# gps10mhz.net
KiCad netlist of a schematic drawn in EAGLE
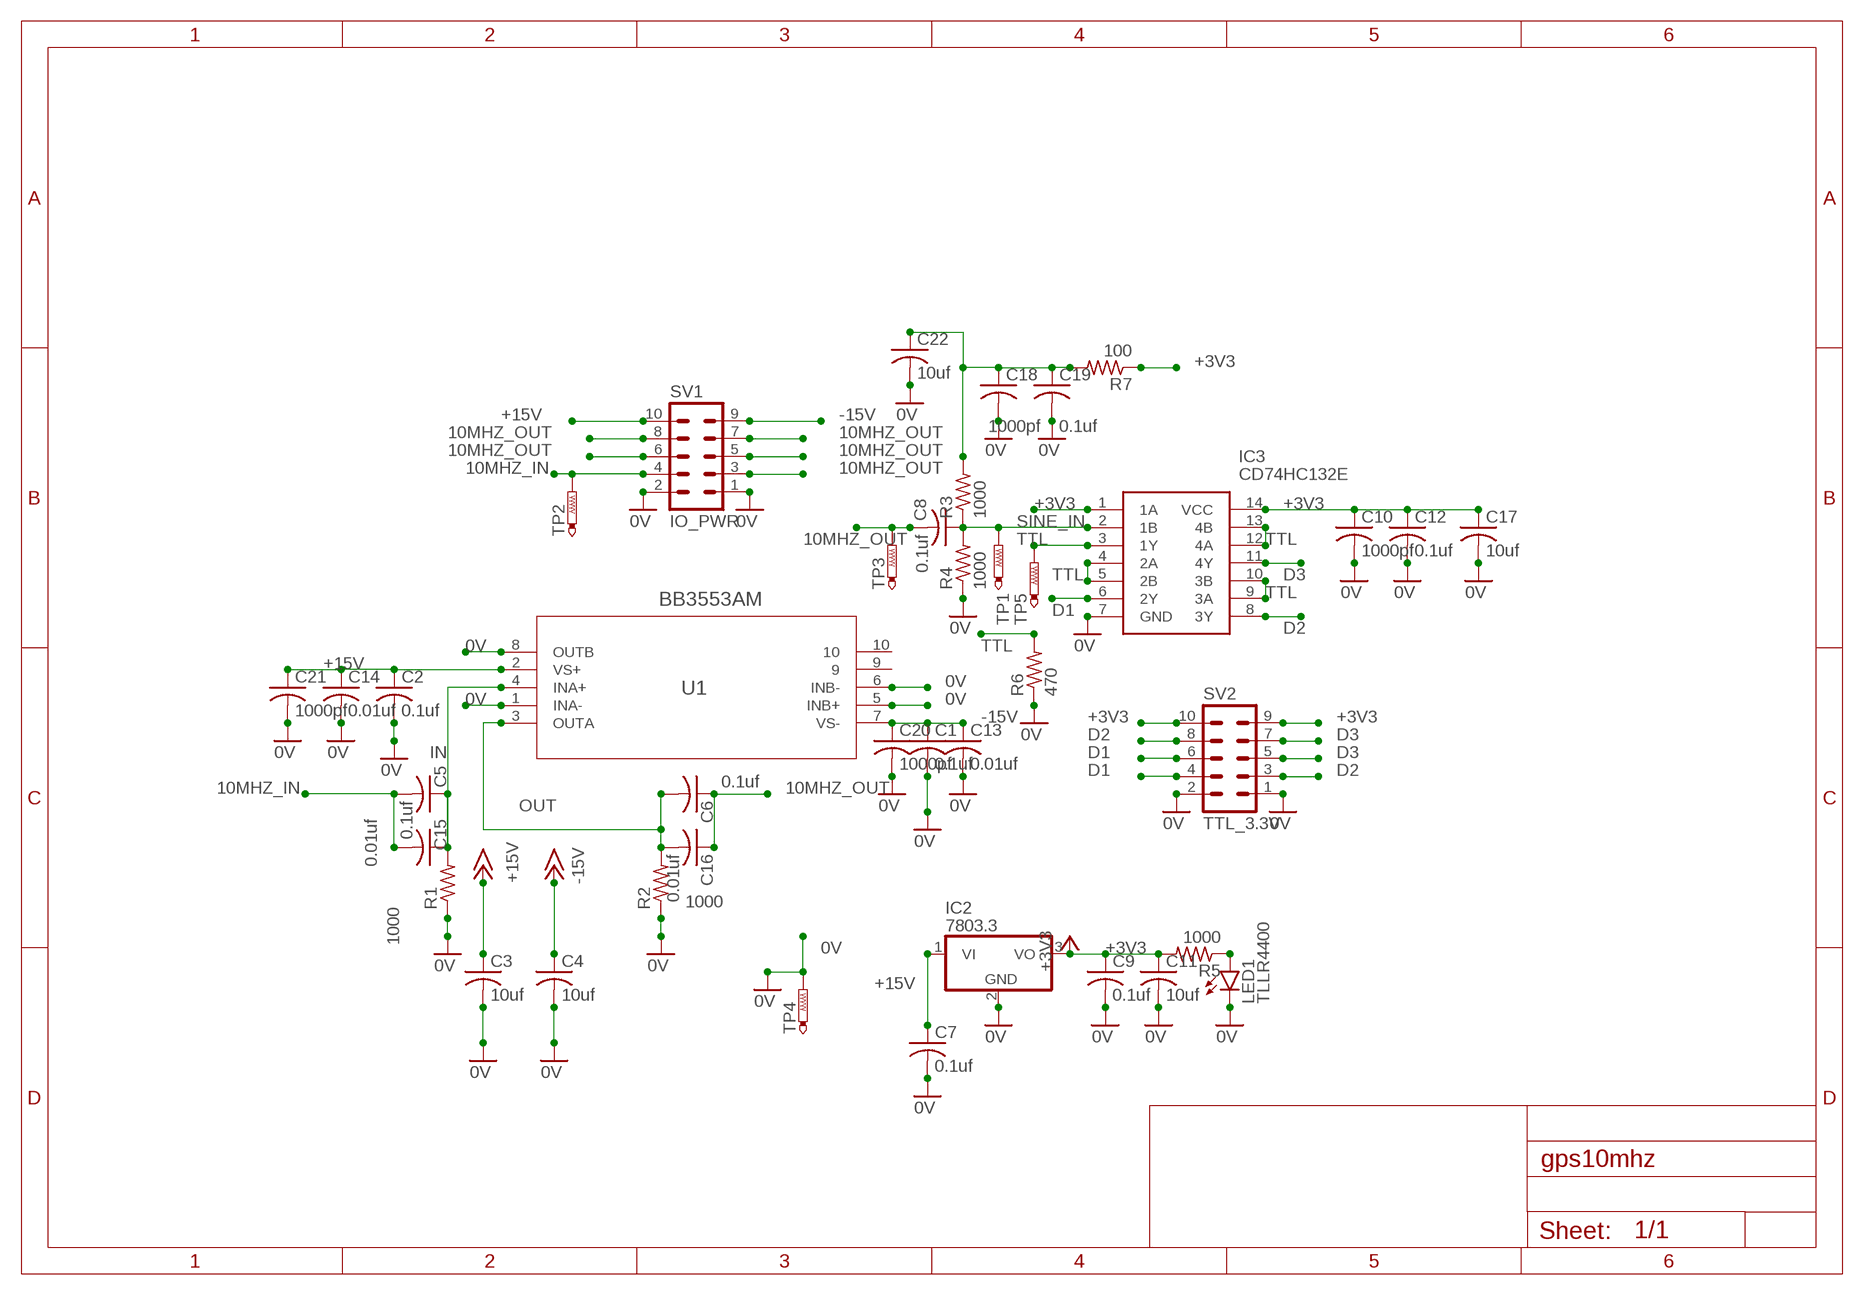
[diagram p0: schematic, sheet 1]

(export (version "E")
  (design (tool "Eeschema 10.0.6"))
  (components
    (comp (ref "C1")
      (value "0.1uf")
      (footprint "eagle-import:C0805")
      (libsource (lib "eagle-import") (part "C-USC0805"))
    )
    (comp (ref "C2")
      (value "0.1uf")
      (footprint "eagle-import:C0805")
      (libsource (lib "eagle-import") (part "C-USC0805"))
    )
    (comp (ref "C3")
      (value "10uf")
      (footprint "eagle-import:C0805")
      (libsource (lib "eagle-import") (part "C-USC0805"))
    )
    (comp (ref "C4")
      (value "10uf")
      (footprint "eagle-import:C0805")
      (libsource (lib "eagle-import") (part "C-USC0805"))
    )
    (comp (ref "C5")
      (value "0.1uf")
      (footprint "eagle-import:C0805")
      (libsource (lib "eagle-import") (part "C-USC0805"))
    )
    (comp (ref "C6")
      (value "0.1uf")
      (footprint "eagle-import:C0805")
      (libsource (lib "eagle-import") (part "C-USC0805"))
    )
    (comp (ref "C7")
      (value "0.1uf")
      (footprint "eagle-import:C0805")
      (libsource (lib "eagle-import") (part "C-USC0805"))
    )
    (comp (ref "C8")
      (value "0.1uf")
      (footprint "eagle-import:C0805")
      (libsource (lib "eagle-import") (part "C-USC0805"))
    )
    (comp (ref "C9")
      (value "0.1uf")
      (footprint "eagle-import:C0805")
      (libsource (lib "eagle-import") (part "C-USC0805"))
    )
    (comp (ref "C10")
      (value "1000pf")
      (footprint "eagle-import:C0805")
      (libsource (lib "eagle-import") (part "C-USC0805"))
    )
    (comp (ref "C11")
      (value "10uf")
      (footprint "eagle-import:C0805")
      (libsource (lib "eagle-import") (part "C-USC0805"))
    )
    (comp (ref "C12")
      (value "0.1uf")
      (footprint "eagle-import:C0805")
      (libsource (lib "eagle-import") (part "C-USC0805"))
    )
    (comp (ref "C13")
      (value "0.01uf")
      (footprint "eagle-import:C0805")
      (libsource (lib "eagle-import") (part "C-USC0805"))
    )
    (comp (ref "C14")
      (value "0.01uf")
      (footprint "eagle-import:C0805")
      (libsource (lib "eagle-import") (part "C-USC0805"))
    )
    (comp (ref "C15")
      (value "0.01uf")
      (footprint "eagle-import:C0805")
      (libsource (lib "eagle-import") (part "C-USC0805"))
    )
    (comp (ref "C16")
      (value "0.01uf")
      (footprint "eagle-import:C0805")
      (libsource (lib "eagle-import") (part "C-USC0805"))
    )
    (comp (ref "C17")
      (value "10uf")
      (footprint "eagle-import:C0805")
      (libsource (lib "eagle-import") (part "C-USC0805"))
    )
    (comp (ref "C18")
      (value "1000pf")
      (footprint "eagle-import:C0805")
      (libsource (lib "eagle-import") (part "C-USC0805"))
    )
    (comp (ref "C19")
      (value "0.1uf")
      (footprint "eagle-import:C0805")
      (libsource (lib "eagle-import") (part "C-USC0805"))
    )
    (comp (ref "C20")
      (value "1000pf")
      (footprint "eagle-import:C0805")
      (libsource (lib "eagle-import") (part "C-USC0805"))
    )
    (comp (ref "C21")
      (value "1000pf")
      (footprint "eagle-import:C0805")
      (libsource (lib "eagle-import") (part "C-USC0805"))
    )
    (comp (ref "C22")
      (value "10uf")
      (footprint "eagle-import:C0805")
      (libsource (lib "eagle-import") (part "C-USC0805"))
    )
    (comp (ref "IC2")
      (value "7803.3")
      (footprint "eagle-import:TO220H")
      (libsource (lib "eagle-import") (part "78T05"))
    )
    (comp (ref "IC3")
      (value "CD74HC132E")
      (footprint "eagle-import:DIP794W53P254L1930H508Q14N")
      (fields (field (name "MOUSER_PART_NUMBER") "595-CD74HC132E"))
      (libsource (lib "eagle-import") (part "CD74HC132E"))
    )
    (comp (ref "LED1")
      (value "TLLR4400")
      (footprint "eagle-import:LED3MM")
      (fields (field (name "MF") "VISHAY SEMICONDUCTOR"))
      (libsource (lib "eagle-import") (part "TLLR4400"))
    )
    (comp (ref "R1")
      (value "1000")
      (footprint "eagle-import:R1206")
      (libsource (lib "eagle-import") (part "R-US_R1206"))
    )
    (comp (ref "R2")
      (value "1000")
      (footprint "eagle-import:R1206")
      (libsource (lib "eagle-import") (part "R-US_R1206"))
    )
    (comp (ref "R3")
      (value "1000")
      (footprint "eagle-import:R1206")
      (libsource (lib "eagle-import") (part "R-US_R1206"))
    )
    (comp (ref "R4")
      (value "1000")
      (footprint "eagle-import:R1206")
      (libsource (lib "eagle-import") (part "R-US_R1206"))
    )
    (comp (ref "R5")
      (value "1000")
      (footprint "eagle-import:R1206")
      (libsource (lib "eagle-import") (part "R-US_R1206"))
    )
    (comp (ref "R6")
      (value "470")
      (footprint "eagle-import:R1206")
      (libsource (lib "eagle-import") (part "R-US_R1206"))
    )
    (comp (ref "R7")
      (value "100")
      (footprint "eagle-import:R1206")
      (libsource (lib "eagle-import") (part "R-US_R1206"))
    )
    (comp (ref "SV1")
      (value "IO_PWR")
      (footprint "eagle-import:MA05-2")
      (libsource (lib "eagle-import") (part "MA05-2"))
    )
    (comp (ref "SV2")
      (value "TTL_3.3V")
      (footprint "eagle-import:MA05-2")
      (libsource (lib "eagle-import") (part "MA05-2"))
    )
    (comp (ref "TP1")
      (value "PTR1PAD1-13")
      (footprint "eagle-import:P1-13")
      (libsource (lib "eagle-import") (part "PTR1PAD1-13"))
    )
    (comp (ref "TP2")
      (value "PTR1PAD1-13")
      (footprint "eagle-import:P1-13")
      (libsource (lib "eagle-import") (part "PTR1PAD1-13"))
    )
    (comp (ref "TP3")
      (value "PTR1PAD1-13")
      (footprint "eagle-import:P1-13")
      (libsource (lib "eagle-import") (part "PTR1PAD1-13"))
    )
    (comp (ref "TP4")
      (value "PTR1PAD1-13")
      (footprint "eagle-import:P1-13")
      (libsource (lib "eagle-import") (part "PTR1PAD1-13"))
    )
    (comp (ref "TP5")
      (value "PTR1PAD1-13")
      (footprint "eagle-import:P1-13")
      (libsource (lib "eagle-import") (part "PTR1PAD1-13"))
    )
    (comp (ref "U1")
      (value "BB3553AM")
      (footprint "eagle-import:LMF8_TEX")
      (fields
        (field (name "MANUFACTURER_PART_NUMBER") "OPA2541AM")
        (field (name "COPYRIGHT") "Copyright (C) 2025 Ultra Librarian. All rights reserved.")
      )
      (libsource (lib "eagle-import") (part "OPA2541AMBB3553AM"))
    )
  )
  (nets
    (net (code "1") (name "+3V3") (class "Default")
      (node (ref "C10") (pin "1") (pinfunction "1_1") (pintype "passive"))
      (node (ref "C11") (pin "1") (pinfunction "1_1") (pintype "passive"))
      (node (ref "C12") (pin "1") (pinfunction "1_1") (pintype "passive"))
      (node (ref "C17") (pin "1") (pinfunction "1_1") (pintype "passive"))
      (node (ref "C9") (pin "1") (pinfunction "1_1") (pintype "passive"))
      (node (ref "IC2") (pin "3") (pinfunction "VO_3") (pintype "passive"))
      (node (ref "IC3") (pin "1") (pinfunction "1A_1") (pintype "bidirectional"))
      (node (ref "IC3") (pin "14") (pinfunction "VCC_14") (pintype "bidirectional"))
      (node (ref "R5") (pin "2") (pinfunction "2_2") (pintype "passive"))
      (node (ref "R7") (pin "1") (pinfunction "1_1") (pintype "passive"))
      (node (ref "SV2") (pin "10") (pinfunction "10_10") (pintype "passive"))
      (node (ref "SV2") (pin "9") (pinfunction "9_9") (pintype "passive"))
    )
    (net (code "2") (name "+15V") (class "Default")
      (node (ref "C14") (pin "1") (pinfunction "1_1") (pintype "passive"))
      (node (ref "C2") (pin "1") (pinfunction "1_1") (pintype "passive"))
      (node (ref "C21") (pin "1") (pinfunction "1_1") (pintype "passive"))
      (node (ref "C3") (pin "1") (pinfunction "1_1") (pintype "passive"))
      (node (ref "C7") (pin "1") (pinfunction "1_1") (pintype "passive"))
      (node (ref "IC2") (pin "1") (pinfunction "VI_1") (pintype "input"))
      (node (ref "SV1") (pin "10") (pinfunction "10_10") (pintype "passive"))
      (node (ref "U1") (pin "2") (pinfunction "VS+_2") (pintype "power_in"))
    )
    (net (code "3") (name "-15V") (class "Default")
      (node (ref "C1") (pin "1") (pinfunction "1_1") (pintype "passive"))
      (node (ref "C13") (pin "1") (pinfunction "1_1") (pintype "passive"))
      (node (ref "C20") (pin "1") (pinfunction "1_1") (pintype "passive"))
      (node (ref "C4") (pin "1") (pinfunction "1_1") (pintype "passive"))
      (node (ref "SV1") (pin "9") (pinfunction "9_9") (pintype "passive"))
      (node (ref "U1") (pin "7") (pinfunction "VS-_7") (pintype "power_in"))
    )
    (net (code "4") (name "/10MHZ_IN") (class "Default")
      (node (ref "C15") (pin "2") (pinfunction "2_2") (pintype "passive"))
      (node (ref "C5") (pin "2") (pinfunction "2_2") (pintype "passive"))
      (node (ref "SV1") (pin "4") (pinfunction "4_4") (pintype "passive"))
      (node (ref "TP2") (pin "TP") (pinfunction "TP_TP") (pintype "input"))
    )
    (net (code "5") (name "/10MHZ_OUT") (class "Default")
      (node (ref "C16") (pin "1") (pinfunction "1_1") (pintype "passive"))
      (node (ref "C6") (pin "1") (pinfunction "1_1") (pintype "passive"))
      (node (ref "C8") (pin "2") (pinfunction "2_2") (pintype "passive"))
      (node (ref "SV1") (pin "3") (pinfunction "3_3") (pintype "passive"))
      (node (ref "SV1") (pin "5") (pinfunction "5_5") (pintype "passive"))
      (node (ref "SV1") (pin "6") (pinfunction "6_6") (pintype "passive"))
      (node (ref "SV1") (pin "7") (pinfunction "7_7") (pintype "passive"))
      (node (ref "SV1") (pin "8") (pinfunction "8_8") (pintype "passive"))
      (node (ref "TP3") (pin "TP") (pinfunction "TP_TP") (pintype "input"))
    )
    (net (code "6") (name "/D1") (class "Default")
      (node (ref "IC3") (pin "6") (pinfunction "2Y_6") (pintype "bidirectional"))
      (node (ref "SV2") (pin "4") (pinfunction "4_4") (pintype "passive"))
      (node (ref "SV2") (pin "6") (pinfunction "6_6") (pintype "passive"))
    )
    (net (code "7") (name "/D2") (class "Default")
      (node (ref "IC3") (pin "8") (pinfunction "3Y_8") (pintype "bidirectional"))
      (node (ref "SV2") (pin "3") (pinfunction "3_3") (pintype "passive"))
      (node (ref "SV2") (pin "8") (pinfunction "8_8") (pintype "passive"))
    )
    (net (code "8") (name "/D3") (class "Default")
      (node (ref "IC3") (pin "11") (pinfunction "4Y_11") (pintype "bidirectional"))
      (node (ref "SV2") (pin "5") (pinfunction "5_5") (pintype "passive"))
      (node (ref "SV2") (pin "7") (pinfunction "7_7") (pintype "passive"))
    )
    (net (code "9") (name "/IN") (class "Default")
      (node (ref "C15") (pin "1") (pinfunction "1_1") (pintype "passive"))
      (node (ref "C5") (pin "1") (pinfunction "1_1") (pintype "passive"))
      (node (ref "R1") (pin "2") (pinfunction "2_2") (pintype "passive"))
      (node (ref "U1") (pin "4") (pinfunction "INA+_4") (pintype "input"))
    )
    (net (code "10") (name "/OUT") (class "Default")
      (node (ref "C16") (pin "2") (pinfunction "2_2") (pintype "passive"))
      (node (ref "C6") (pin "2") (pinfunction "2_2") (pintype "passive"))
      (node (ref "R2") (pin "2") (pinfunction "2_2") (pintype "passive"))
      (node (ref "U1") (pin "3") (pinfunction "OUTA_3") (pintype "output"))
    )
    (net (code "11") (name "/SINE_IN") (class "Default")
      (node (ref "C8") (pin "1") (pinfunction "1_1") (pintype "passive"))
      (node (ref "IC3") (pin "2") (pinfunction "1B_2") (pintype "bidirectional"))
      (node (ref "R3") (pin "1") (pinfunction "1_1") (pintype "passive"))
      (node (ref "R4") (pin "2") (pinfunction "2_2") (pintype "passive"))
      (node (ref "TP1") (pin "TP") (pinfunction "TP_TP") (pintype "input"))
    )
    (net (code "12") (name "/TTL") (class "Default")
      (node (ref "IC3") (pin "10") (pinfunction "3B_10") (pintype "bidirectional"))
      (node (ref "IC3") (pin "12") (pinfunction "4A_12") (pintype "bidirectional"))
      (node (ref "IC3") (pin "13") (pinfunction "4B_13") (pintype "bidirectional"))
      (node (ref "IC3") (pin "3") (pinfunction "1Y_3") (pintype "bidirectional"))
      (node (ref "IC3") (pin "4") (pinfunction "2A_4") (pintype "bidirectional"))
      (node (ref "IC3") (pin "5") (pinfunction "2B_5") (pintype "bidirectional"))
      (node (ref "IC3") (pin "9") (pinfunction "3A_9") (pintype "bidirectional"))
      (node (ref "R6") (pin "2") (pinfunction "2_2") (pintype "passive"))
      (node (ref "TP5") (pin "TP") (pinfunction "TP_TP") (pintype "input"))
    )
    (net (code "13") (name "0V") (class "Default")
      (node (ref "C1") (pin "2") (pinfunction "2_2") (pintype "passive"))
      (node (ref "C10") (pin "2") (pinfunction "2_2") (pintype "passive"))
      (node (ref "C11") (pin "2") (pinfunction "2_2") (pintype "passive"))
      (node (ref "C12") (pin "2") (pinfunction "2_2") (pintype "passive"))
      (node (ref "C13") (pin "2") (pinfunction "2_2") (pintype "passive"))
      (node (ref "C14") (pin "2") (pinfunction "2_2") (pintype "passive"))
      (node (ref "C17") (pin "2") (pinfunction "2_2") (pintype "passive"))
      (node (ref "C18") (pin "2") (pinfunction "2_2") (pintype "passive"))
      (node (ref "C19") (pin "2") (pinfunction "2_2") (pintype "passive"))
      (node (ref "C2") (pin "2") (pinfunction "2_2") (pintype "passive"))
      (node (ref "C20") (pin "2") (pinfunction "2_2") (pintype "passive"))
      (node (ref "C21") (pin "2") (pinfunction "2_2") (pintype "passive"))
      (node (ref "C22") (pin "2") (pinfunction "2_2") (pintype "passive"))
      (node (ref "C3") (pin "2") (pinfunction "2_2") (pintype "passive"))
      (node (ref "C4") (pin "2") (pinfunction "2_2") (pintype "passive"))
      (node (ref "C7") (pin "2") (pinfunction "2_2") (pintype "passive"))
      (node (ref "C9") (pin "2") (pinfunction "2_2") (pintype "passive"))
      (node (ref "IC2") (pin "2") (pinfunction "GND_2") (pintype "passive"))
      (node (ref "IC3") (pin "7") (pinfunction "GND_7") (pintype "bidirectional"))
      (node (ref "LED1") (pin "K") (pinfunction "C_K") (pintype "passive"))
      (node (ref "R1") (pin "1") (pinfunction "1_1") (pintype "passive"))
      (node (ref "R2") (pin "1") (pinfunction "1_1") (pintype "passive"))
      (node (ref "R4") (pin "1") (pinfunction "1_1") (pintype "passive"))
      (node (ref "R6") (pin "1") (pinfunction "1_1") (pintype "passive"))
      (node (ref "SV1") (pin "1") (pinfunction "1_1") (pintype "passive"))
      (node (ref "SV1") (pin "2") (pinfunction "2_2") (pintype "passive"))
      (node (ref "SV2") (pin "1") (pinfunction "1_1") (pintype "passive"))
      (node (ref "SV2") (pin "2") (pinfunction "2_2") (pintype "passive"))
      (node (ref "TP4") (pin "TP") (pinfunction "TP_TP") (pintype "input"))
      (node (ref "U1") (pin "1") (pinfunction "INA-_1") (pintype "input"))
      (node (ref "U1") (pin "5") (pinfunction "INB+_5") (pintype "input"))
      (node (ref "U1") (pin "6") (pinfunction "INB-_6") (pintype "input"))
      (node (ref "U1") (pin "8") (pinfunction "OUTB_8") (pintype "output"))
    )
    (net (code "14") (name "Net-(C18-Pad1)") (class "Default")
      (node (ref "C18") (pin "1") (pinfunction "1_1") (pintype "passive"))
      (node (ref "C19") (pin "1") (pinfunction "1_1") (pintype "passive"))
      (node (ref "C22") (pin "1") (pinfunction "1_1") (pintype "passive"))
      (node (ref "R3") (pin "2") (pinfunction "2_2") (pintype "passive"))
      (node (ref "R7") (pin "2") (pinfunction "2_2") (pintype "passive"))
    )
    (net (code "15") (name "Net-(LED1-PadA)") (class "Default")
      (node (ref "LED1") (pin "A") (pinfunction "A_A") (pintype "passive"))
      (node (ref "R5") (pin "1") (pinfunction "1_1") (pintype "passive"))
    )
    (net (code "16") (name "unconnected-(U1-Pad9)") (class "Default")
      (node (ref "U1") (pin "9") (pinfunction "9_9") (pintype "passive"))
    )
    (net (code "17") (name "unconnected-(U1-Pad10)") (class "Default")
      (node (ref "U1") (pin "10") (pinfunction "10_10") (pintype "passive"))
    )
  )
)
